# 01_-_Power_Supply.net
KiCad netlist of a schematic drawn in Altium Designer
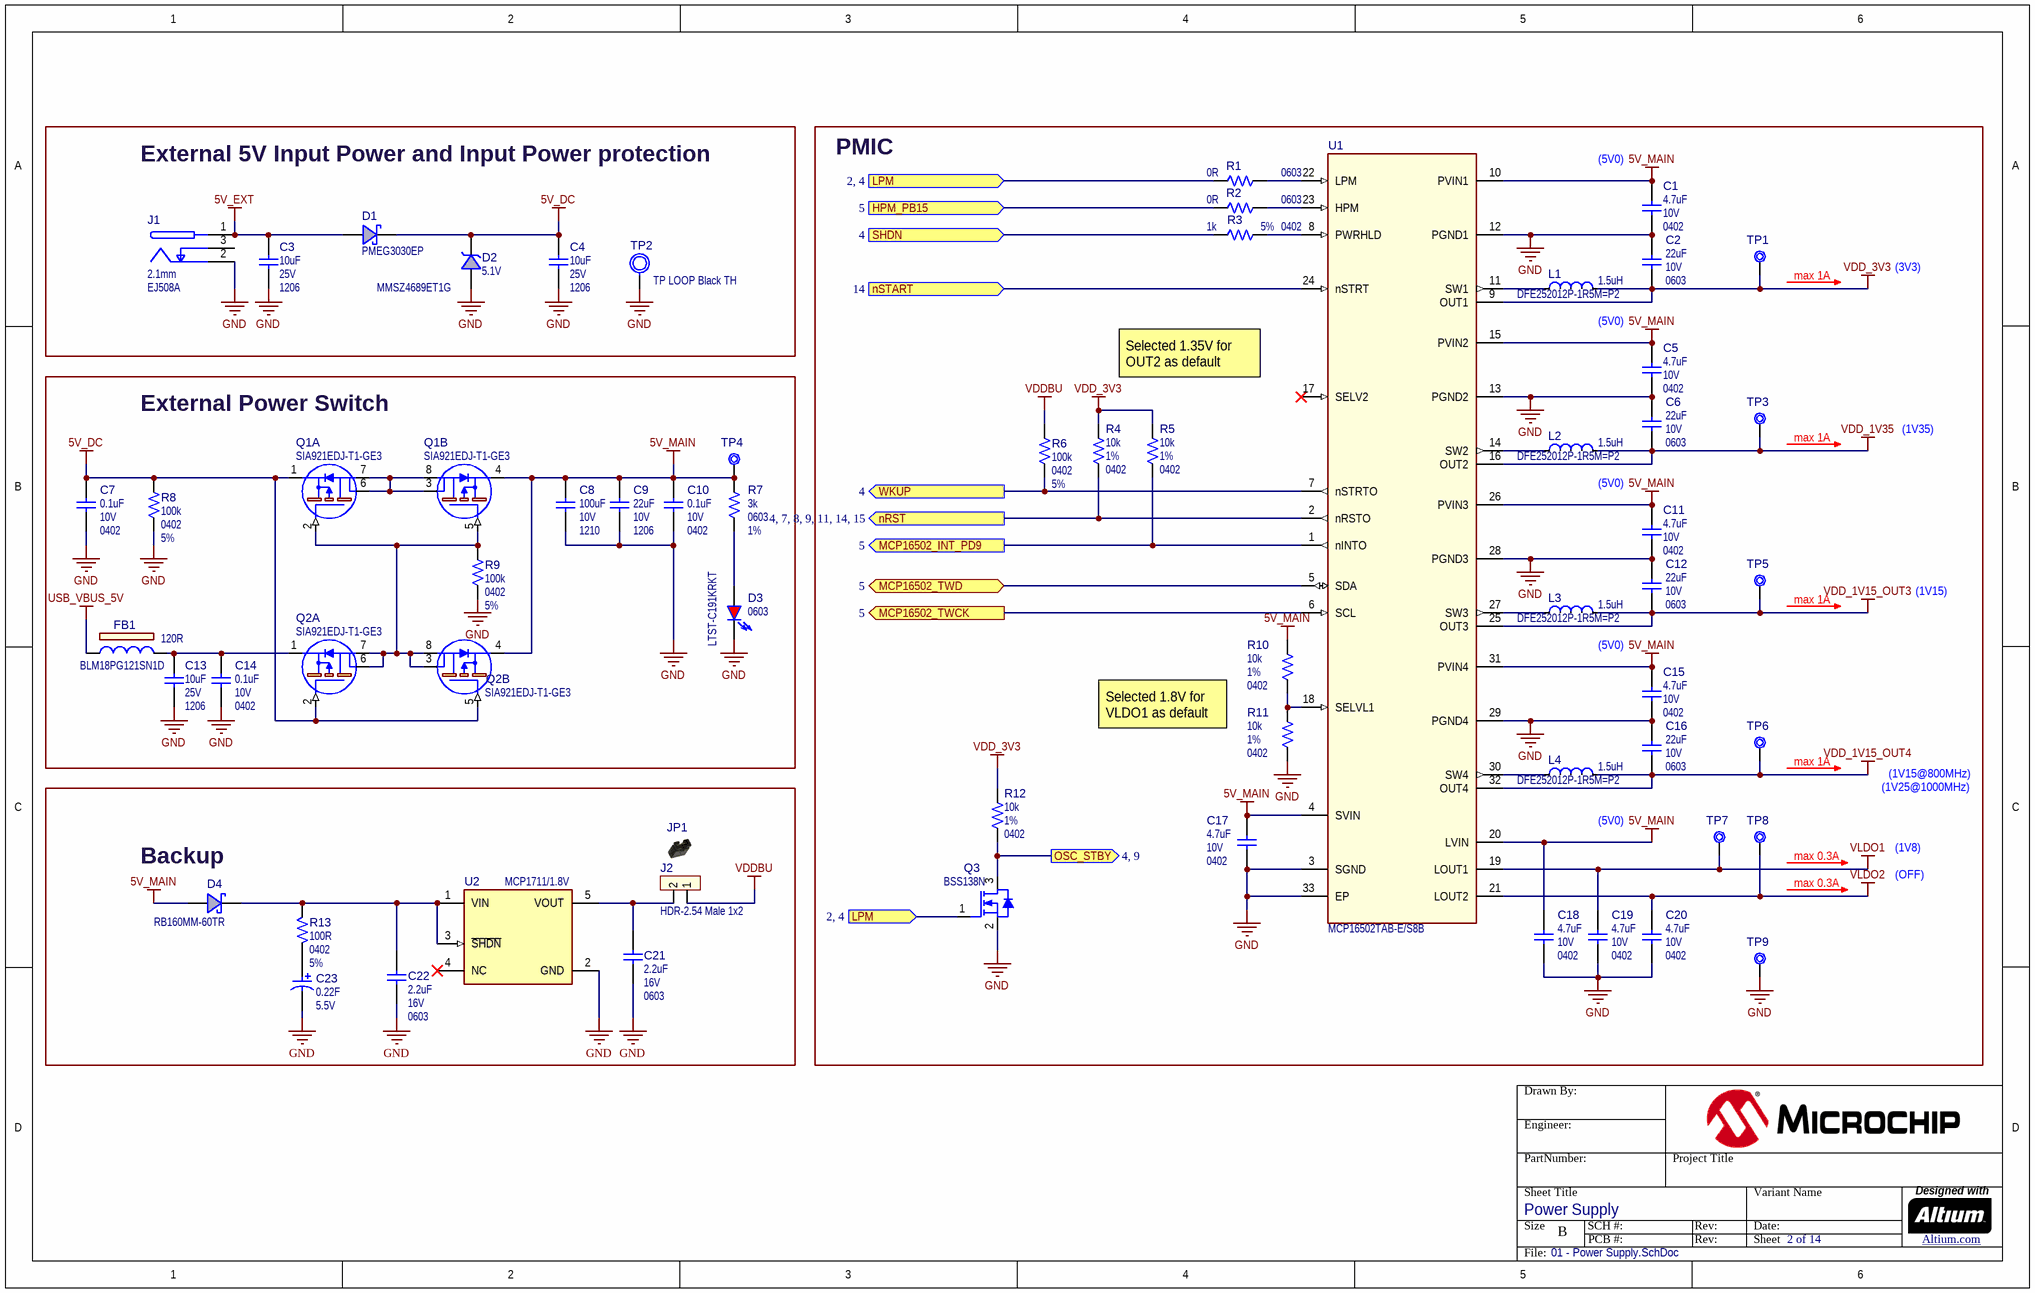
[diagram p0: 01 - Power Supply.SchDoc]

(export (version "E")
  (design (tool "Eeschema 10.0.6"))
  (components
    (comp (ref "C1")
      (value "4.7uF")
      (footprint "CAP_C_0402")
      (description "Capacitor")
      (fields
        (field (name "VOLTAGE") "10V")
        (field (name "PACKAGE") "0402")
        (field (name "TOLERANCE") "10%")
        (field (name "Comment") "Capacitor NP")
        (field (name "OWNER") "Jesus Aviles")
      )
      (libsource (lib "MCHP-CDB") (part "Capacitor NP"))
    )
    (comp (ref "C2")
      (value "22uF")
      (footprint "CAP_C_0603")
      (description "Capacitor")
      (fields
        (field (name "VOLTAGE") "10V")
        (field (name "PACKAGE") "0603")
        (field (name "TOLERANCE") "20%")
        (field (name "Comment") "Capacitor NP")
        (field (name "OWNER") "Razvan Cristescu")
      )
      (libsource (lib "MCHP-CDB") (part "Capacitor NP"))
    )
    (comp (ref "C3")
      (value "10uF")
      (footprint "CAP_C_1206")
      (description "Capacitor")
      (fields
        (field (name "VOLTAGE") "25V")
        (field (name "PACKAGE") "1206")
        (field (name "TOLERANCE") "10%")
        (field (name "Comment") "Capacitor NP")
        (field (name "OWNER") "Sorin Stanoaia")
      )
      (libsource (lib "MCHP-CDB") (part "Capacitor NP"))
    )
    (comp (ref "C4")
      (value "10uF")
      (footprint "CAP_C_1206")
      (description "Capacitor")
      (fields
        (field (name "VOLTAGE") "25V")
        (field (name "PACKAGE") "1206")
        (field (name "TOLERANCE") "10%")
        (field (name "Comment") "Capacitor NP")
        (field (name "OWNER") "Sorin Stanoaia")
      )
      (libsource (lib "MCHP-CDB") (part "Capacitor NP"))
    )
    (comp (ref "C5")
      (value "4.7uF")
      (footprint "CAP_C_0402")
      (description "Capacitor")
      (fields
        (field (name "VOLTAGE") "10V")
        (field (name "PACKAGE") "0402")
        (field (name "TOLERANCE") "10%")
        (field (name "Comment") "Capacitor NP")
        (field (name "OWNER") "Jesus Aviles")
      )
      (libsource (lib "MCHP-CDB") (part "Capacitor NP"))
    )
    (comp (ref "C6")
      (value "22uF")
      (footprint "CAP_C_0603")
      (description "Capacitor")
      (fields
        (field (name "VOLTAGE") "10V")
        (field (name "PACKAGE") "0603")
        (field (name "TOLERANCE") "20%")
        (field (name "Comment") "Capacitor NP")
        (field (name "OWNER") "Razvan Cristescu")
      )
      (libsource (lib "MCHP-CDB") (part "Capacitor NP"))
    )
    (comp (ref "C7")
      (value "0.1uF")
      (footprint "CAP_C_0402")
      (description "Capacitor")
      (fields
        (field (name "VOLTAGE") "10V")
        (field (name "PACKAGE") "0402")
        (field (name "TOLERANCE") "10%")
        (field (name "Comment") "Capacitor NP")
        (field (name "OWNER") "Tad Ahlvers")
      )
      (libsource (lib "MCHP-CDB") (part "Capacitor NP"))
    )
    (comp (ref "C8")
      (value "100uF")
      (footprint "CAP_C_1210")
      (description "Capacitor")
      (fields
        (field (name "VOLTAGE") "10V")
        (field (name "PACKAGE") "1210")
        (field (name "TOLERANCE") "20%")
        (field (name "Comment") "Capacitor NP")
      )
      (libsource (lib "MCHP-CDB") (part "Capacitor NP"))
    )
    (comp (ref "C9")
      (value "22uF")
      (footprint "CAP_C_1206")
      (description "Capacitor")
      (fields
        (field (name "VOLTAGE") "10V")
        (field (name "PACKAGE") "1206")
        (field (name "TOLERANCE") "10%")
        (field (name "Comment") "Capacitor NP")
        (field (name "OWNER") "Bogdan Popescu")
      )
      (libsource (lib "MCHP-CDB") (part "Capacitor NP"))
    )
    (comp (ref "C10")
      (value "0.1uF")
      (footprint "CAP_C_0402")
      (description "Capacitor")
      (fields
        (field (name "VOLTAGE") "10V")
        (field (name "PACKAGE") "0402")
        (field (name "TOLERANCE") "10%")
        (field (name "Comment") "Capacitor NP")
        (field (name "OWNER") "Tad Ahlvers")
      )
      (libsource (lib "MCHP-CDB") (part "Capacitor NP"))
    )
    (comp (ref "C11")
      (value "4.7uF")
      (footprint "CAP_C_0402")
      (description "Capacitor")
      (fields
        (field (name "VOLTAGE") "10V")
        (field (name "PACKAGE") "0402")
        (field (name "TOLERANCE") "10%")
        (field (name "Comment") "Capacitor NP")
        (field (name "OWNER") "Jesus Aviles")
      )
      (libsource (lib "MCHP-CDB") (part "Capacitor NP"))
    )
    (comp (ref "C12")
      (value "22uF")
      (footprint "CAP_C_0603")
      (description "Capacitor")
      (fields
        (field (name "VOLTAGE") "10V")
        (field (name "PACKAGE") "0603")
        (field (name "TOLERANCE") "20%")
        (field (name "Comment") "Capacitor NP")
        (field (name "OWNER") "Razvan Cristescu")
      )
      (libsource (lib "MCHP-CDB") (part "Capacitor NP"))
    )
    (comp (ref "C13")
      (value "10uF")
      (footprint "CAP_C_1206")
      (description "Capacitor")
      (fields
        (field (name "VOLTAGE") "25V")
        (field (name "PACKAGE") "1206")
        (field (name "TOLERANCE") "10%")
        (field (name "Comment") "Capacitor NP")
        (field (name "OWNER") "Sorin Stanoaia")
      )
      (libsource (lib "MCHP-CDB") (part "Capacitor NP"))
    )
    (comp (ref "C14")
      (value "0.1uF")
      (footprint "CAP_C_0402")
      (description "Capacitor")
      (fields
        (field (name "VOLTAGE") "10V")
        (field (name "PACKAGE") "0402")
        (field (name "TOLERANCE") "10%")
        (field (name "Comment") "Capacitor NP")
        (field (name "OWNER") "Tad Ahlvers")
      )
      (libsource (lib "MCHP-CDB") (part "Capacitor NP"))
    )
    (comp (ref "C15")
      (value "4.7uF")
      (footprint "CAP_C_0402")
      (description "Capacitor")
      (fields
        (field (name "VOLTAGE") "10V")
        (field (name "PACKAGE") "0402")
        (field (name "TOLERANCE") "10%")
        (field (name "Comment") "Capacitor NP")
        (field (name "OWNER") "Jesus Aviles")
      )
      (libsource (lib "MCHP-CDB") (part "Capacitor NP"))
    )
    (comp (ref "C16")
      (value "22uF")
      (footprint "CAP_C_0603")
      (description "Capacitor")
      (fields
        (field (name "VOLTAGE") "10V")
        (field (name "PACKAGE") "0603")
        (field (name "TOLERANCE") "20%")
        (field (name "Comment") "Capacitor NP")
        (field (name "OWNER") "Razvan Cristescu")
      )
      (libsource (lib "MCHP-CDB") (part "Capacitor NP"))
    )
    (comp (ref "C17")
      (value "4.7uF")
      (footprint "CAP_C_0402")
      (description "Capacitor")
      (fields
        (field (name "VOLTAGE") "10V")
        (field (name "PACKAGE") "0402")
        (field (name "TOLERANCE") "10%")
        (field (name "Comment") "Capacitor NP")
        (field (name "OWNER") "Jesus Aviles")
      )
      (libsource (lib "MCHP-CDB") (part "Capacitor NP"))
    )
    (comp (ref "C18")
      (value "4.7uF")
      (footprint "CAP_C_0402")
      (description "Capacitor")
      (fields
        (field (name "VOLTAGE") "10V")
        (field (name "PACKAGE") "0402")
        (field (name "TOLERANCE") "10%")
        (field (name "Comment") "Capacitor NP")
        (field (name "OWNER") "Jesus Aviles")
      )
      (libsource (lib "MCHP-CDB") (part "Capacitor NP"))
    )
    (comp (ref "C19")
      (value "4.7uF")
      (footprint "CAP_C_0402")
      (description "Capacitor")
      (fields
        (field (name "VOLTAGE") "10V")
        (field (name "PACKAGE") "0402")
        (field (name "TOLERANCE") "10%")
        (field (name "Comment") "Capacitor NP")
        (field (name "OWNER") "Jesus Aviles")
      )
      (libsource (lib "MCHP-CDB") (part "Capacitor NP"))
    )
    (comp (ref "C20")
      (value "4.7uF")
      (footprint "CAP_C_0402")
      (description "Capacitor")
      (fields
        (field (name "VOLTAGE") "10V")
        (field (name "PACKAGE") "0402")
        (field (name "TOLERANCE") "10%")
        (field (name "Comment") "Capacitor NP")
        (field (name "OWNER") "Jesus Aviles")
      )
      (libsource (lib "MCHP-CDB") (part "Capacitor NP"))
    )
    (comp (ref "C21")
      (value "2.2uF")
      (footprint "CAP_C_0603")
      (description "Capacitor")
      (fields
        (field (name "VOLTAGE") "16V")
        (field (name "PACKAGE") "0603")
        (field (name "TOLERANCE") "10%")
        (field (name "Comment") "Capacitor NP")
      )
      (libsource (lib "MCHP-CDB") (part "Capacitor NP"))
    )
    (comp (ref "C22")
      (value "2.2uF")
      (footprint "CAP_C_0603")
      (description "Capacitor")
      (fields
        (field (name "VOLTAGE") "16V")
        (field (name "PACKAGE") "0603")
        (field (name "TOLERANCE") "10%")
        (field (name "Comment") "Capacitor NP")
      )
      (libsource (lib "MCHP-CDB") (part "Capacitor NP"))
    )
    (comp (ref "C23")
      (value "0.22F")
      (footprint "CAP_AX_KR-5R5V224-R")
      (description "Capacitor")
      (fields
        (field (name "VOLTAGE") "5.5V")
        (field (name "TOLERANCE") "-20% to +80%")
        (field (name "Comment") "Capacitor POL")
        (field (name "OWNER") "Dragos Danaila")
      )
      (libsource (lib "MCHP-CDB") (part "Capacitor POL"))
    )
    (comp (ref "D1")
      (value "PMEG3030EP")
      (footprint "SOD-128")
      (fields (field (name "Comment") "Diode Schottky") (field (name "OWNER") "Mark Loper"))
      (libsource (lib "MCHP-CDB") (part "Diode Schottky"))
    )
    (comp (ref "D2")
      (value "5.1V")
      (footprint "SOD-123")
      (fields
        (field (name "POWER") "500mW")
        (field (name "MANUFACTURER PART NUMBER 1") "MMSZ4689ET1G")
        (field (name "Comment") "Diode Zener")
        (field (name "OWNER") "Cristian Papuc")
      )
      (libsource (lib "MCHP-CDB") (part "Diode Zener"))
    )
    (comp (ref "D3")
      (value "LED_red")
      (footprint "LED_0603_RED")
      (description "LED")
      (fields
        (field (name "PACKAGE") "0603")
        (field (name "MANUFACTURER PART NUMBER 1") "LTST-C191KRKT")
        (field (name "OWNER") "Sompoch Loboonlert")
      )
      (libsource (lib "MCHP-CDB") (part "LED_red"))
    )
    (comp (ref "D4")
      (value "RB160MM-60TR")
      (footprint "SOD-123FL")
      (description "DIO SCTKY RB160M-60TR 550mV 1A 60V SMD SOD-123F")
      (fields
        (field (name "POWER") "1W")
        (field (name "Comment") "Diode Schottky")
        (field (name "OWNER") "Ciprian Abramov")
      )
      (libsource (lib "MCHP-CDB") (part "Diode Schottky"))
    )
    (comp (ref "FB1")
      (value "120R")
      (footprint "IND_C_0603")
      (fields
        (field (name "MANUFACTURER PART NUMBER 1") "BLM18PG121SN1D")
        (field (name "Comment") "Ferrite Bead")
        (field (name "OWNER") "Petnarong Chaijaroong")
      )
      (libsource (lib "MCHP-CDB") (part "Ferrite Bead"))
    )
    (comp (ref "J1")
      (value "2.1mm")
      (footprint "CON_JACK_POWER_TH_RA_MPD_EJ508A")
      (fields
        (field (name "MANUFACTURER PART NUMBER 1") "EJ508A")
        (field (name "Comment") "CON JACK 2C 3P SPST")
        (field (name "OWNER") "Mark Loper")
      )
      (libsource (lib "MCHP-CDB") (part "CON JACK 2C 3P SPST"))
    )
    (comp (ref "J2")
      (value "HDR-2.54 Male 1x2")
      (footprint "HDR_M_2.54_1x2")
      (fields (field (name "Comment") "Header 1x2") (field (name "OWNER") "Ilie Galan"))
      (libsource (lib "MCHP-CDB") (part "Header 1x2"))
    )
    (comp (ref "JP1")
      (value "Jumper Mechanical")
      (footprint "Jumper_Mechanical")
      (fields (field (name "OWNER") "Narasimha Murthy"))
      (libsource (lib "MCHP-CDB") (part "Jumper Mechanical"))
    )
    (comp (ref "L1")
      (value "1.5uH")
      (footprint "IND_C_1008")
      (description "Inductor")
      (fields
        (field (name "MANUFACTURER PART NUMBER 1") "DFE252012P-1R5M=P2")
        (field (name "OWNER") "Razvan Cristescu")
      )
      (libsource (lib "MCHP-CDB") (part "Inductor"))
    )
    (comp (ref "L2")
      (value "1.5uH")
      (footprint "IND_C_1008")
      (description "Inductor")
      (fields
        (field (name "MANUFACTURER PART NUMBER 1") "DFE252012P-1R5M=P2")
        (field (name "OWNER") "Razvan Cristescu")
      )
      (libsource (lib "MCHP-CDB") (part "Inductor"))
    )
    (comp (ref "L3")
      (value "1.5uH")
      (footprint "IND_C_1008")
      (description "Inductor")
      (fields
        (field (name "MANUFACTURER PART NUMBER 1") "DFE252012P-1R5M=P2")
        (field (name "OWNER") "Razvan Cristescu")
      )
      (libsource (lib "MCHP-CDB") (part "Inductor"))
    )
    (comp (ref "L4")
      (value "1.5uH")
      (footprint "IND_C_1008")
      (description "Inductor")
      (fields
        (field (name "MANUFACTURER PART NUMBER 1") "DFE252012P-1R5M=P2")
        (field (name "OWNER") "Razvan Cristescu")
      )
      (libsource (lib "MCHP-CDB") (part "Inductor"))
    )
    (comp (ref "Q1")
      (value "SIA923AEDJ-T1-GE3")
      (footprint "SiA923AEDJ PPAK_SC70_6L")
      (fields
        (field (name "POWER") "7.8W")
        (field (name "VOLTAGE") "20V")
        (field (name "MANUFACTURER PART NUMBER 1") "SIA921EDJ-T1-GE3")
        (field (name "OWNER") "Ciprian Abramov")
      )
      (libsource (lib "") (part "Transistor MOS-P+P Dual SIA923AEDJ-T1-GE3_1"))
    )
    (comp (ref "Q2")
      (value "SIA923AEDJ-T1-GE3")
      (footprint "SiA923AEDJ PPAK_SC70_6L")
      (fields
        (field (name "POWER") "7.8W")
        (field (name "VOLTAGE") "20V")
        (field (name "MANUFACTURER PART NUMBER 1") "SIA921EDJ-T1-GE3")
        (field (name "OWNER") "Ciprian Abramov")
      )
      (libsource (lib "MCHP-CDB") (part "Transistor MOS-P+P Dual SIA923AEDJ-T1-GE3"))
    )
    (comp (ref "Q3")
      (value "BSS138N")
      (footprint "SOT-23-3")
      (description "Transistor MOS")
      (fields
        (field (name "POWER") "0.36W")
        (field (name "VOLTAGE") "60V")
        (field (name "OWNER") "Dragos Danaila")
      )
      (libsource (lib "MCHP-CDB") (part "Transistor MOS-N GSD"))
    )
    (comp (ref "R1")
      (value "0R")
      (footprint "RES_C_0603")
      (description "Resistor")
      (fields (field (name "PACKAGE") "0603") (field (name "POWER") "1/10W"))
      (libsource (lib "MCHP-CDB") (part "Resistor"))
    )
    (comp (ref "R2")
      (value "0R")
      (footprint "RES_C_0603")
      (description "Resistor")
      (fields (field (name "PACKAGE") "0603") (field (name "POWER") "1/10W"))
      (libsource (lib "MCHP-CDB") (part "Resistor"))
    )
    (comp (ref "R3")
      (value "1k")
      (footprint "RES_C_0402")
      (description "Resistor")
      (fields
        (field (name "PACKAGE") "0402")
        (field (name "TOLERANCE") "5%")
        (field (name "VOLTAGE") "50V")
        (field (name "POWER") "1/16W")
        (field (name "OWNER") "Tad Ahlvers")
      )
      (libsource (lib "MCHP-CDB") (part "Resistor"))
    )
    (comp (ref "R4")
      (value "10k")
      (footprint "RES_C_0402")
      (description "Resistor")
      (fields
        (field (name "PACKAGE") "0402")
        (field (name "TOLERANCE") "1%")
        (field (name "VOLTAGE") "50V")
        (field (name "POWER") "1/10W")
        (field (name "OWNER") "Brent Lanphear")
      )
      (libsource (lib "MCHP-CDB") (part "Resistor"))
    )
    (comp (ref "R5")
      (value "10k")
      (footprint "RES_C_0402")
      (description "Resistor")
      (fields
        (field (name "PACKAGE") "0402")
        (field (name "TOLERANCE") "1%")
        (field (name "VOLTAGE") "50V")
        (field (name "POWER") "1/10W")
        (field (name "OWNER") "Brent Lanphear")
      )
      (libsource (lib "MCHP-CDB") (part "Resistor"))
    )
    (comp (ref "R6")
      (value "100k")
      (footprint "RES_C_0402")
      (description "Resistor")
      (fields
        (field (name "PACKAGE") "0402")
        (field (name "TOLERANCE") "5%")
        (field (name "POWER") "1/10W")
        (field (name "VOLTAGE") "50V")
      )
      (libsource (lib "MCHP-CDB") (part "Resistor"))
    )
    (comp (ref "R7")
      (value "3k")
      (footprint "RES_C_0603")
      (description "Resistor")
      (fields
        (field (name "PACKAGE") "0603")
        (field (name "TOLERANCE") "1%")
        (field (name "VOLTAGE") "75V")
        (field (name "POWER") "1/10W")
        (field (name "OWNER") "Bogdan P (M91398)")
      )
      (libsource (lib "MCHP-CDB") (part "Resistor"))
    )
    (comp (ref "R8")
      (value "100k")
      (footprint "RES_C_0402")
      (description "Resistor")
      (fields
        (field (name "PACKAGE") "0402")
        (field (name "TOLERANCE") "5%")
        (field (name "POWER") "1/10W")
        (field (name "VOLTAGE") "50V")
      )
      (libsource (lib "MCHP-CDB") (part "Resistor"))
    )
    (comp (ref "R9")
      (value "100k")
      (footprint "RES_C_0402")
      (description "Resistor")
      (fields
        (field (name "PACKAGE") "0402")
        (field (name "TOLERANCE") "5%")
        (field (name "POWER") "1/10W")
        (field (name "VOLTAGE") "50V")
      )
      (libsource (lib "MCHP-CDB") (part "Resistor"))
    )
    (comp (ref "R10")
      (value "10k")
      (footprint "RES_C_0402")
      (description "Resistor")
      (fields
        (field (name "PACKAGE") "0402")
        (field (name "TOLERANCE") "1%")
        (field (name "VOLTAGE") "50V")
        (field (name "POWER") "1/10W")
        (field (name "OWNER") "Brent Lanphear")
      )
      (libsource (lib "MCHP-CDB") (part "Resistor"))
    )
    (comp (ref "R11")
      (value "10k")
      (footprint "RES_C_0402")
      (description "Resistor")
      (fields
        (field (name "PACKAGE") "0402")
        (field (name "TOLERANCE") "1%")
        (field (name "VOLTAGE") "50V")
        (field (name "POWER") "1/10W")
        (field (name "OWNER") "Brent Lanphear")
      )
      (libsource (lib "MCHP-CDB") (part "Resistor"))
    )
    (comp (ref "R12")
      (value "10k")
      (footprint "RES_C_0402")
      (description "Resistor")
      (fields
        (field (name "PACKAGE") "0402")
        (field (name "TOLERANCE") "1%")
        (field (name "VOLTAGE") "50V")
        (field (name "POWER") "1/10W")
        (field (name "OWNER") "Brent Lanphear")
      )
      (libsource (lib "MCHP-CDB") (part "Resistor"))
    )
    (comp (ref "R13")
      (value "100R")
      (footprint "RES_C_0402")
      (description "Resistor")
      (fields
        (field (name "PACKAGE") "0402")
        (field (name "TOLERANCE") "5%")
        (field (name "VOLTAGE") "50V")
        (field (name "POWER") "1/16W")
        (field (name "OWNER") "Dragos Danaila")
      )
      (libsource (lib "MCHP-CDB") (part "Resistor"))
    )
    (comp (ref "TP1")
      (value "Test Point No BOM")
      (footprint "TP_1mm_SMD")
      (description "Test Point")
      (fields (field (name "OWNER") "Cristian Papuc"))
      (libsource (lib "MCHP-CDB") (part "Test Point No BOM"))
    )
    (comp (ref "TP2")
      (value "TP LOOP Black TH")
      (footprint "CON_TP_TH_V_BLK_KEC_5011")
      (description "Test Point")
      (fields (field (name "Comment") "GND") (field (name "OWNER") "Tad Ahlvers"))
      (libsource (lib "MCHP-CDB") (part "Test Point"))
    )
    (comp (ref "TP3")
      (value "Test Point No BOM")
      (footprint "TP_1mm_SMD")
      (description "Test Point")
      (fields (field (name "OWNER") "Cristian Papuc"))
      (libsource (lib "MCHP-CDB") (part "Test Point No BOM"))
    )
    (comp (ref "TP4")
      (value "Test Point No BOM")
      (footprint "TP_1mm_SMD")
      (description "Test Point")
      (fields (field (name "OWNER") "Cristian Papuc"))
      (libsource (lib "MCHP-CDB") (part "Test Point No BOM"))
    )
    (comp (ref "TP5")
      (value "Test Point No BOM")
      (footprint "TP_1mm_SMD")
      (description "Test Point")
      (fields (field (name "OWNER") "Cristian Papuc"))
      (libsource (lib "MCHP-CDB") (part "Test Point No BOM"))
    )
    (comp (ref "TP6")
      (value "Test Point No BOM")
      (footprint "TP_1mm_SMD")
      (description "Test Point")
      (fields (field (name "OWNER") "Cristian Papuc"))
      (libsource (lib "MCHP-CDB") (part "Test Point No BOM"))
    )
    (comp (ref "TP7")
      (value "Test Point No BOM")
      (footprint "TP_1mm_SMD")
      (description "Test Point")
      (fields (field (name "OWNER") "Cristian Papuc"))
      (libsource (lib "MCHP-CDB") (part "Test Point No BOM"))
    )
    (comp (ref "TP8")
      (value "Test Point No BOM")
      (footprint "TP_1mm_SMD")
      (description "Test Point")
      (fields (field (name "OWNER") "Cristian Papuc"))
      (libsource (lib "MCHP-CDB") (part "Test Point No BOM"))
    )
    (comp (ref "TP9")
      (value "Test Point No BOM")
      (footprint "TP_1mm_SMD")
      (description "Test Point")
      (fields (field (name "OWNER") "Cristian Papuc"))
      (libsource (lib "MCHP-CDB") (part "Test Point No BOM"))
    )
    (comp (ref "U1")
      (value "MCP16502TAB-E/S8B")
      (footprint "QFN-32_5X5_EP3.7X3.7")
      (fields (field (name "Comment") "MCP16502 QFN-32") (field (name "OWNER") "Dragos Danaila"))
      (libsource (lib "MCHP-CDB") (part "MCP16502 QFN-32"))
    )
    (comp (ref "U2")
      (value "MCP1711/1.8V")
      (footprint "SOT-23-5")
      (description "LDO MCP1711")
      (fields (field (name "Comment") "MCP1711 SOT-23-5") (field (name "OWNER") "Sorin Stanoaia"))
      (libsource (lib "MCHP-CDB") (part "MCP1711 SOT-23-5"))
    )
  )
  (nets
    (net (code "1") (name "/HPM_PB15") (class "Default")
      (node (ref "R2") (pin "2") (pinfunction "2_2") (pintype "passive"))
    )
    (net (code "2") (name "/LPM") (class "Default")
      (node (ref "Q3") (pin "1") (pinfunction "G_1") (pintype "passive"))
      (node (ref "R1") (pin "1") (pinfunction "1_1") (pintype "passive"))
    )
    (net (code "3") (name "/MCP16502_INT_PD9") (class "Default")
      (node (ref "R5") (pin "1") (pinfunction "1_1") (pintype "passive"))
      (node (ref "U1") (pin "1") (pinfunction "nINTO_1") (pintype "output"))
    )
    (net (code "4") (name "/MCP16502_TWCK") (class "Default")
      (node (ref "U1") (pin "6") (pinfunction "SCL_6") (pintype "input"))
    )
    (net (code "5") (name "/MCP16502_TWD") (class "Default")
      (node (ref "U1") (pin "5") (pinfunction "SDA_5") (pintype "bidirectional"))
    )
    (net (code "6") (name "/OSC_STBY") (class "Default")
      (node (ref "Q3") (pin "3") (pinfunction "D_3") (pintype "passive"))
      (node (ref "R12") (pin "1") (pinfunction "1_1") (pintype "passive"))
    )
    (net (code "7") (name "/SHDN") (class "Default")
      (node (ref "R3") (pin "2") (pinfunction "2_2") (pintype "passive"))
    )
    (net (code "8") (name "/WKUP") (class "Default")
      (node (ref "R6") (pin "1") (pinfunction "1_1") (pintype "passive"))
      (node (ref "U1") (pin "7") (pinfunction "nSTRTO_7") (pintype "output"))
    )
    (net (code "9") (name "/nRST") (class "Default")
      (node (ref "R4") (pin "1") (pinfunction "1_1") (pintype "passive"))
      (node (ref "U1") (pin "2") (pinfunction "nRSTO_2") (pintype "output"))
    )
    (net (code "10") (name "/nSTART") (class "Default")
      (node (ref "U1") (pin "24") (pinfunction "nSTRT_24") (pintype "input"))
    )
    (net (code "11") (name "5V_DC") (class "Default")
      (node (ref "C4") (pin "1") (pinfunction "1_1") (pintype "passive"))
      (node (ref "C7") (pin "2") (pinfunction "2_2") (pintype "passive"))
      (node (ref "D1") (pin "2") (pinfunction "K_2") (pintype "passive"))
      (node (ref "D2") (pin "2") (pinfunction "K_2") (pintype "passive"))
      (node (ref "Q1") (pin "1") (pinfunction "S1_1") (pintype "passive"))
      (node (ref "Q2") (pin "2") (pinfunction "G1_2") (pintype "input"))
      (node (ref "Q2") (pin "5") (pinfunction "G2_5") (pintype "input"))
      (node (ref "R8") (pin "2") (pinfunction "2_2") (pintype "passive"))
    )
    (net (code "12") (name "5V_EXT") (class "Default")
      (node (ref "C3") (pin "1") (pinfunction "1_1") (pintype "passive"))
      (node (ref "D1") (pin "1") (pinfunction "A_1") (pintype "passive"))
      (node (ref "J1") (pin "1") (pinfunction "PLUS_1") (pintype "passive"))
    )
    (net (code "13") (name "5V_MAIN") (class "Default")
      (node (ref "C1") (pin "2") (pinfunction "2_2") (pintype "passive"))
      (node (ref "C10") (pin "2") (pinfunction "2_2") (pintype "passive"))
      (node (ref "C11") (pin "2") (pinfunction "2_2") (pintype "passive"))
      (node (ref "C15") (pin "2") (pinfunction "2_2") (pintype "passive"))
      (node (ref "C17") (pin "2") (pinfunction "2_2") (pintype "passive"))
      (node (ref "C18") (pin "2") (pinfunction "2_2") (pintype "passive"))
      (node (ref "C5") (pin "2") (pinfunction "2_2") (pintype "passive"))
      (node (ref "C8") (pin "2") (pinfunction "2_2") (pintype "passive"))
      (node (ref "C9") (pin "2") (pinfunction "2_2") (pintype "passive"))
      (node (ref "D4") (pin "1") (pinfunction "A_1") (pintype "passive"))
      (node (ref "Q1") (pin "4") (pinfunction "S2_4") (pintype "passive"))
      (node (ref "Q2") (pin "4") (pinfunction "S2_4") (pintype "passive"))
      (node (ref "R10") (pin "2") (pinfunction "2_2") (pintype "passive"))
      (node (ref "R7") (pin "1") (pinfunction "1_1") (pintype "passive"))
      (node (ref "TP4") (pin "1") (pinfunction "1_1") (pintype "passive"))
      (node (ref "U1") (pin "10") (pinfunction "PVIN1_10") (pintype "power_in"))
      (node (ref "U1") (pin "15") (pinfunction "PVIN2_15") (pintype "power_in"))
      (node (ref "U1") (pin "20") (pinfunction "LVIN_20") (pintype "power_in"))
      (node (ref "U1") (pin "26") (pinfunction "PVIN3_26") (pintype "power_in"))
      (node (ref "U1") (pin "31") (pinfunction "PVIN4_31") (pintype "power_in"))
      (node (ref "U1") (pin "4") (pinfunction "SVIN_4") (pintype "power_in"))
    )
    (net (code "14") (name "GND") (class "Default")
      (node (ref "C1") (pin "1") (pinfunction "1_1") (pintype "passive"))
      (node (ref "C10") (pin "1") (pinfunction "1_1") (pintype "passive"))
      (node (ref "C11") (pin "1") (pinfunction "1_1") (pintype "passive"))
      (node (ref "C12") (pin "2") (pinfunction "2_2") (pintype "passive"))
      (node (ref "C13") (pin "2") (pinfunction "2_2") (pintype "passive"))
      (node (ref "C14") (pin "1") (pinfunction "1_1") (pintype "passive"))
      (node (ref "C15") (pin "1") (pinfunction "1_1") (pintype "passive"))
      (node (ref "C16") (pin "2") (pinfunction "2_2") (pintype "passive"))
      (node (ref "C17") (pin "1") (pinfunction "1_1") (pintype "passive"))
      (node (ref "C18") (pin "1") (pinfunction "1_1") (pintype "passive"))
      (node (ref "C19") (pin "1") (pinfunction "1_1") (pintype "passive"))
      (node (ref "C2") (pin "2") (pinfunction "2_2") (pintype "passive"))
      (node (ref "C20") (pin "1") (pinfunction "1_1") (pintype "passive"))
      (node (ref "C21") (pin "1") (pinfunction "1_1") (pintype "passive"))
      (node (ref "C22") (pin "1") (pinfunction "1_1") (pintype "passive"))
      (node (ref "C23") (pin "2") (pinfunction "2_2") (pintype "passive"))
      (node (ref "C3") (pin "2") (pinfunction "2_2") (pintype "passive"))
      (node (ref "C4") (pin "2") (pinfunction "2_2") (pintype "passive"))
      (node (ref "C5") (pin "1") (pinfunction "1_1") (pintype "passive"))
      (node (ref "C6") (pin "2") (pinfunction "2_2") (pintype "passive"))
      (node (ref "C7") (pin "1") (pinfunction "1_1") (pintype "passive"))
      (node (ref "C8") (pin "1") (pinfunction "1_1") (pintype "passive"))
      (node (ref "C9") (pin "1") (pinfunction "1_1") (pintype "passive"))
      (node (ref "D2") (pin "1") (pinfunction "A_1") (pintype "passive"))
      (node (ref "D3") (pin "2") (pinfunction "K_2") (pintype "passive"))
      (node (ref "J1") (pin "2") (pinfunction "COM_2") (pintype "passive"))
      (node (ref "Q3") (pin "2") (pinfunction "S_2") (pintype "passive"))
      (node (ref "R11") (pin "1") (pinfunction "1_1") (pintype "passive"))
      (node (ref "R8") (pin "1") (pinfunction "1_1") (pintype "passive"))
      (node (ref "R9") (pin "1") (pinfunction "1_1") (pintype "passive"))
      (node (ref "TP2") (pin "1") (pinfunction "1_1") (pintype "passive"))
      (node (ref "TP9") (pin "1") (pinfunction "1_1") (pintype "passive"))
      (node (ref "U1") (pin "12") (pinfunction "PGND1_12") (pintype "power_in"))
      (node (ref "U1") (pin "13") (pinfunction "PGND2_13") (pintype "power_in"))
      (node (ref "U1") (pin "28") (pinfunction "PGND3_28") (pintype "power_in"))
      (node (ref "U1") (pin "29") (pinfunction "PGND4_29") (pintype "power_in"))
      (node (ref "U1") (pin "3") (pinfunction "SGND_3") (pintype "power_in"))
      (node (ref "U1") (pin "33") (pinfunction "EP_33") (pintype "power_in"))
      (node (ref "U2") (pin "2") (pinfunction "GND_2") (pintype "power_in"))
    )
    (net (code "15") (name "Net-(C23-Pad1)") (class "Default")
      (node (ref "C23") (pin "1") (pinfunction "1_1") (pintype "passive"))
      (node (ref "R13") (pin "2") (pinfunction "2_2") (pintype "passive"))
    )
    (net (code "16") (name "Net-(D3-A)") (class "Default")
      (node (ref "D3") (pin "1") (pinfunction "A_1") (pintype "passive"))
      (node (ref "R7") (pin "2") (pinfunction "2_2") (pintype "passive"))
    )
    (net (code "17") (name "Net-(D4-K)") (class "Default")
      (node (ref "C22") (pin "2") (pinfunction "2_2") (pintype "passive"))
      (node (ref "D4") (pin "2") (pinfunction "K_2") (pintype "passive"))
      (node (ref "R13") (pin "1") (pinfunction "1_1") (pintype "passive"))
      (node (ref "U2") (pin "1") (pinfunction "VIN_1") (pintype "power_in"))
      (node (ref "U2") (pin "3") (pinfunction "~{SHDN}_3") (pintype "input"))
    )
    (net (code "18") (name "Net-(L1-S)") (class "Default")
      (node (ref "L1") (pin "1") (pinfunction "S_1") (pintype "passive"))
      (node (ref "U1") (pin "11") (pinfunction "SW1_11") (pintype "output"))
    )
    (net (code "19") (name "Net-(L2-S)") (class "Default")
      (node (ref "L2") (pin "1") (pinfunction "S_1") (pintype "passive"))
      (node (ref "U1") (pin "14") (pinfunction "SW2_14") (pintype "output"))
    )
    (net (code "20") (name "Net-(L3-S)") (class "Default")
      (node (ref "L3") (pin "1") (pinfunction "S_1") (pintype "passive"))
      (node (ref "U1") (pin "27") (pinfunction "SW3_27") (pintype "output"))
    )
    (net (code "21") (name "Net-(L4-S)") (class "Default")
      (node (ref "L4") (pin "1") (pinfunction "S_1") (pintype "passive"))
      (node (ref "U1") (pin "30") (pinfunction "SW4_30") (pintype "output"))
    )
    (net (code "22") (name "Net-(Q1A-D1)") (class "Default")
      (node (ref "Q1") (pin "3") (pinfunction "D2_3") (pintype "passive"))
      (node (ref "Q1") (pin "6") (pinfunction "D1_6") (pintype "passive"))
      (node (ref "Q1") (pin "7") (pinfunction "D1_2_7") (pintype "passive"))
      (node (ref "Q1") (pin "8") (pinfunction "D2_2_8") (pintype "passive"))
    )
    (net (code "23") (name "Net-(Q1A-G1)") (class "Default")
      (node (ref "Q1") (pin "2") (pinfunction "G1_2") (pintype "input"))
      (node (ref "Q1") (pin "5") (pinfunction "G2_5") (pintype "input"))
      (node (ref "Q2") (pin "3") (pinfunction "D2_3") (pintype "passive"))
      (node (ref "Q2") (pin "6") (pinfunction "D1_6") (pintype "passive"))
      (node (ref "Q2") (pin "7") (pinfunction "D1_2_7") (pintype "passive"))
      (node (ref "Q2") (pin "8") (pinfunction "D2_2_8") (pintype "passive"))
      (node (ref "R9") (pin "2") (pinfunction "2_2") (pintype "passive"))
    )
    (net (code "24") (name "Net-(Q2A-S1)") (class "Default")
      (node (ref "C13") (pin "1") (pinfunction "1_1") (pintype "passive"))
      (node (ref "C14") (pin "2") (pinfunction "2_2") (pintype "passive"))
      (node (ref "FB1") (pin "2") (pinfunction "2_2") (pintype "passive"))
      (node (ref "Q2") (pin "1") (pinfunction "S1_1") (pintype "passive"))
    )
    (net (code "25") (name "Net-(U1-HPM)") (class "Default")
      (node (ref "R2") (pin "1") (pinfunction "1_1") (pintype "passive"))
      (node (ref "U1") (pin "23") (pinfunction "HPM_23") (pintype "input"))
    )
    (net (code "26") (name "Net-(U1-LPM)") (class "Default")
      (node (ref "R1") (pin "2") (pinfunction "2_2") (pintype "passive"))
      (node (ref "U1") (pin "22") (pinfunction "LPM_22") (pintype "input"))
    )
    (net (code "27") (name "Net-(U1-PWRHLD)") (class "Default")
      (node (ref "R3") (pin "1") (pinfunction "1_1") (pintype "passive"))
      (node (ref "U1") (pin "8") (pinfunction "PWRHLD_8") (pintype "input"))
    )
    (net (code "28") (name "Net-(U1-SELVL1)") (class "Default")
      (node (ref "R10") (pin "1") (pinfunction "1_1") (pintype "passive"))
      (node (ref "R11") (pin "2") (pinfunction "2_2") (pintype "passive"))
      (node (ref "U1") (pin "18") (pinfunction "SELVL1_18") (pintype "input"))
    )
    (net (code "29") (name "Net-(U2-VOUT)") (class "Default")
      (node (ref "C21") (pin "2") (pinfunction "2_2") (pintype "passive"))
      (node (ref "J2") (pin "2") (pinfunction "2_2") (pintype "passive"))
      (node (ref "U2") (pin "5") (pinfunction "VOUT_5") (pintype "power_in"))
    )
    (net (code "30") (name "USB_VBUS_5V") (class "Default")
      (node (ref "FB1") (pin "1") (pinfunction "1_1") (pintype "passive"))
    )
    (net (code "31") (name "VDDBU") (class "Default")
      (node (ref "J2") (pin "1") (pinfunction "1_1") (pintype "passive"))
      (node (ref "R6") (pin "2") (pinfunction "2_2") (pintype "passive"))
    )
    (net (code "32") (name "VDD_1V15_OUT3") (class "Default")
      (node (ref "C12") (pin "1") (pinfunction "1_1") (pintype "passive"))
      (node (ref "L3") (pin "2") (pinfunction "F_2") (pintype "passive"))
      (node (ref "TP5") (pin "1") (pinfunction "1_1") (pintype "passive"))
      (node (ref "U1") (pin "25") (pinfunction "OUT3_25") (pintype "power_in"))
    )
    (net (code "33") (name "VDD_1V15_OUT4") (class "Default")
      (node (ref "C16") (pin "1") (pinfunction "1_1") (pintype "passive"))
      (node (ref "L4") (pin "2") (pinfunction "F_2") (pintype "passive"))
      (node (ref "TP6") (pin "1") (pinfunction "1_1") (pintype "passive"))
      (node (ref "U1") (pin "32") (pinfunction "OUT4_32") (pintype "power_in"))
    )
    (net (code "34") (name "VDD_1V35") (class "Default")
      (node (ref "C6") (pin "1") (pinfunction "1_1") (pintype "passive"))
      (node (ref "L2") (pin "2") (pinfunction "F_2") (pintype "passive"))
      (node (ref "TP3") (pin "1") (pinfunction "1_1") (pintype "passive"))
      (node (ref "U1") (pin "16") (pinfunction "OUT2_16") (pintype "power_in"))
    )
    (net (code "35") (name "VDD_3V3") (class "Default")
      (node (ref "C2") (pin "1") (pinfunction "1_1") (pintype "passive"))
      (node (ref "L1") (pin "2") (pinfunction "F_2") (pintype "passive"))
      (node (ref "R12") (pin "2") (pinfunction "2_2") (pintype "passive"))
      (node (ref "R4") (pin "2") (pinfunction "2_2") (pintype "passive"))
      (node (ref "R5") (pin "2") (pinfunction "2_2") (pintype "passive"))
      (node (ref "TP1") (pin "1") (pinfunction "1_1") (pintype "passive"))
      (node (ref "U1") (pin "9") (pinfunction "OUT1_9") (pintype "power_in"))
    )
    (net (code "36") (name "VLDO1") (class "Default")
      (node (ref "C19") (pin "2") (pinfunction "2_2") (pintype "passive"))
      (node (ref "TP7") (pin "1") (pinfunction "1_1") (pintype "passive"))
      (node (ref "U1") (pin "19") (pinfunction "LOUT1_19") (pintype "power_in"))
    )
    (net (code "37") (name "VLDO2") (class "Default")
      (node (ref "C20") (pin "2") (pinfunction "2_2") (pintype "passive"))
      (node (ref "TP8") (pin "1") (pinfunction "1_1") (pintype "passive"))
      (node (ref "U1") (pin "21") (pinfunction "LOUT2_21") (pintype "power_in"))
    )
    (net (code "38") (name "unconnected-(J1-SWITCH-Pad3)") (class "Default")
      (node (ref "J1") (pin "3") (pinfunction "SWITCH_3") (pintype "passive"))
    )
    (net (code "39") (name "unconnected-(U1-SELV2-Pad17)") (class "Default")
      (node (ref "U1") (pin "17") (pinfunction "SELV2_17") (pintype "input+no_connect"))
    )
    (net (code "40") (name "unconnected-(U2-NC-Pad4)") (class "Default")
      (node (ref "U2") (pin "4") (pinfunction "NC_4") (pintype "power_in+no_connect"))
    )
  )
)
